# SD_A2.net
KiCad netlist of a schematic drawn in EAGLE
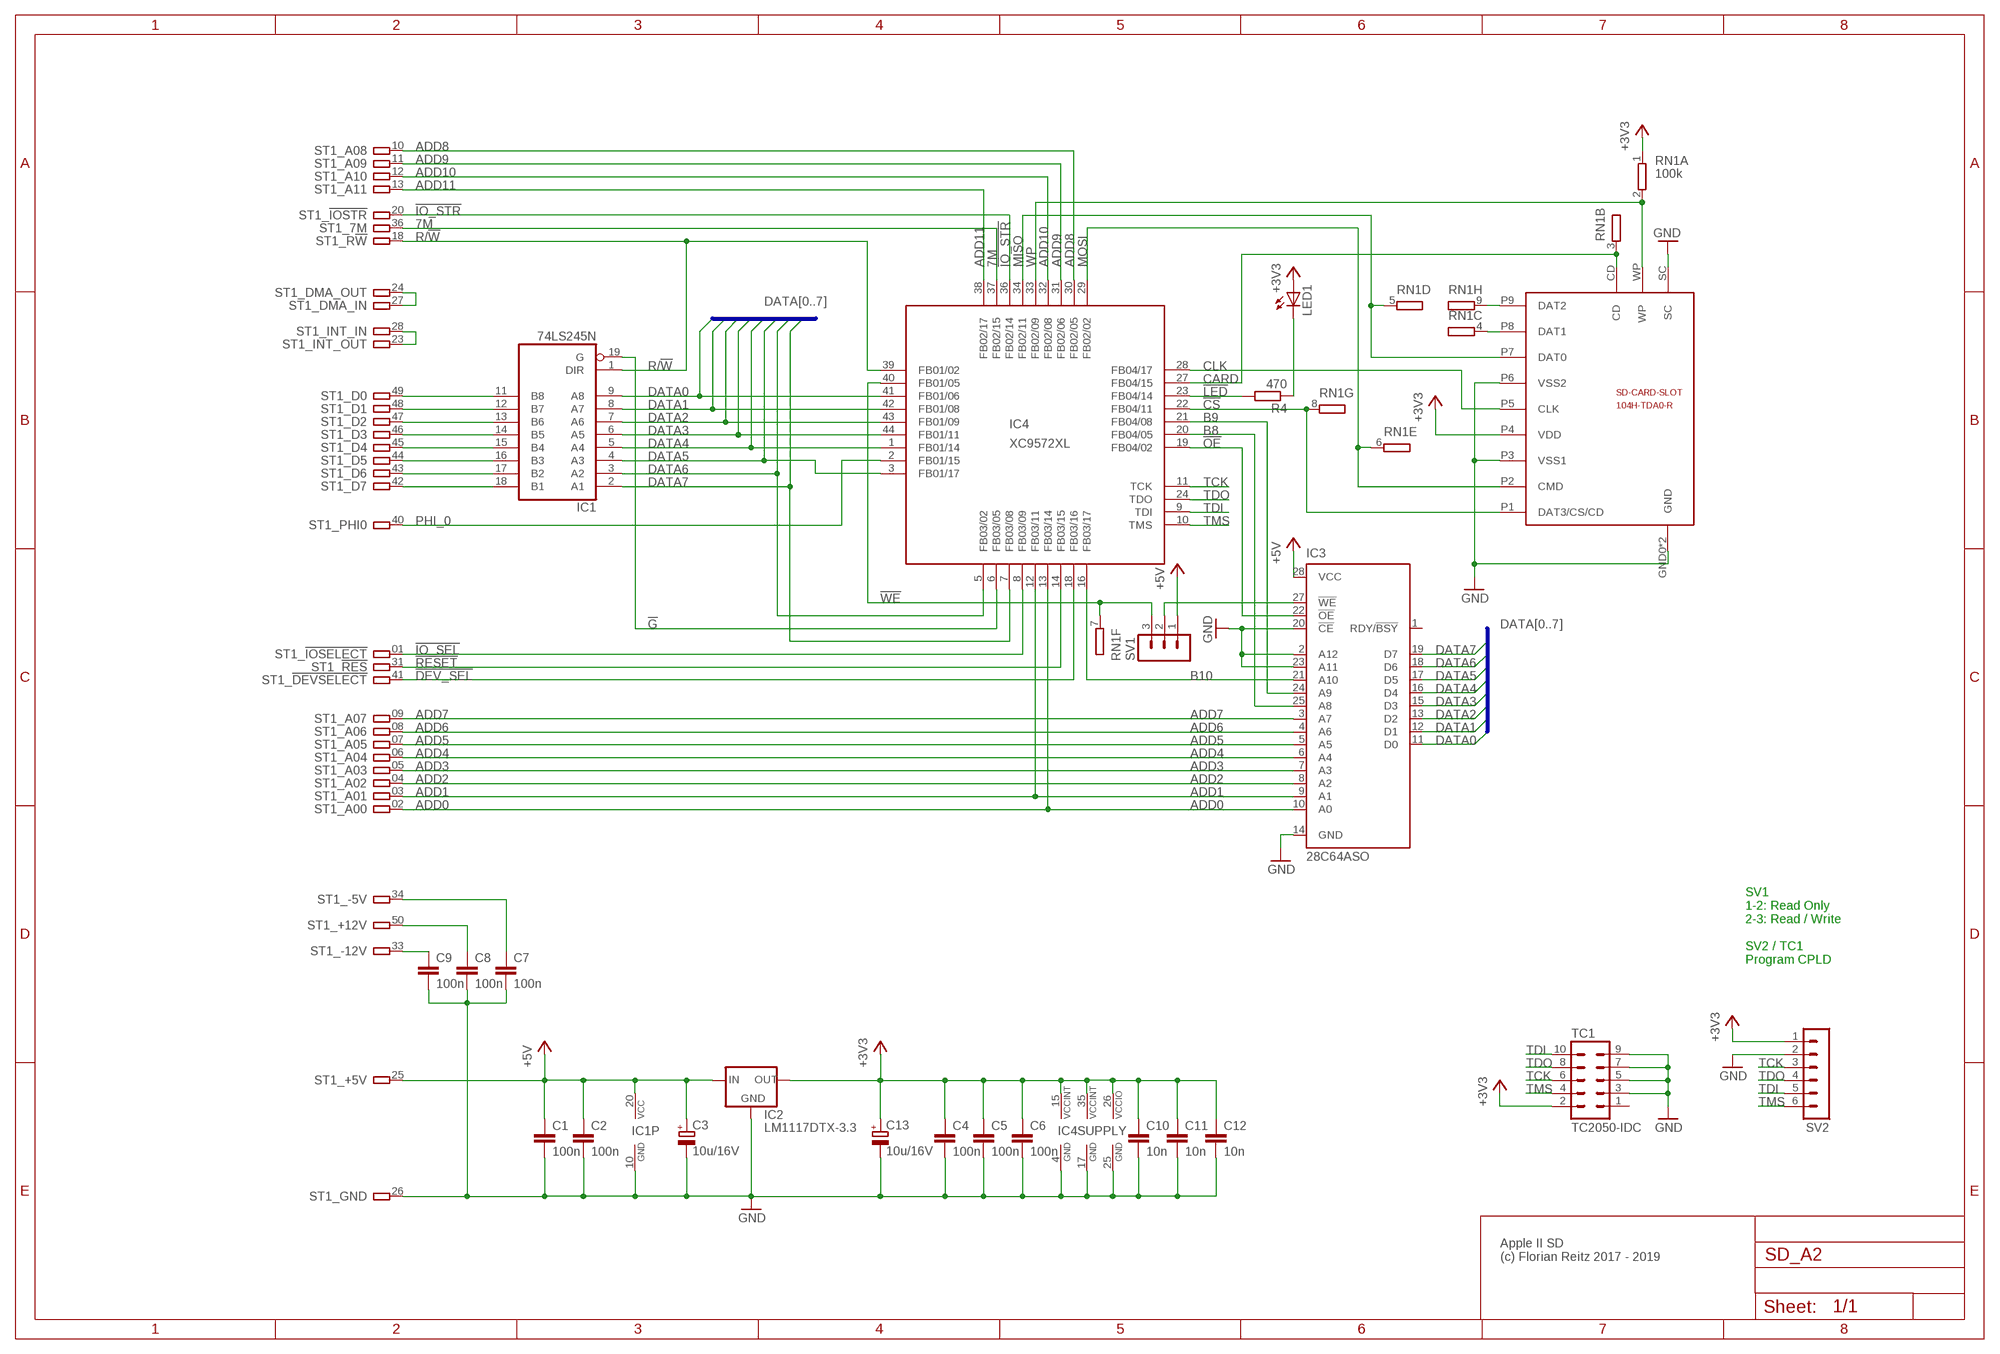
[diagram p0: schematic, sheet 1]

(export (version "E")
  (design (tool "Eeschema 10.0.6"))
  (components
    (comp (ref "C1")
      (value "100n")
      (footprint "eagle-import:C0603K")
      (libsource (lib "eagle-import") (part "C-EUC0603K"))
    )
    (comp (ref "C2")
      (value "100n")
      (footprint "eagle-import:C0603K")
      (libsource (lib "eagle-import") (part "C-EUC0603K"))
    )
    (comp (ref "C3")
      (value "10u/16V")
      (footprint "eagle-import:A_3216-18R")
      (libsource (lib "eagle-import") (part "CPOL-EUA/3216-18R"))
    )
    (comp (ref "C4")
      (value "100n")
      (footprint "eagle-import:C0603K")
      (libsource (lib "eagle-import") (part "C-EUC0603K"))
    )
    (comp (ref "C5")
      (value "100n")
      (footprint "eagle-import:C0603K")
      (libsource (lib "eagle-import") (part "C-EUC0603K"))
    )
    (comp (ref "C6")
      (value "100n")
      (footprint "eagle-import:C0603K")
      (libsource (lib "eagle-import") (part "C-EUC0603K"))
    )
    (comp (ref "C7")
      (value "100n")
      (footprint "eagle-import:C0603K")
      (libsource (lib "eagle-import") (part "C-EUC0603K"))
    )
    (comp (ref "C8")
      (value "100n")
      (footprint "eagle-import:C0603K")
      (libsource (lib "eagle-import") (part "C-EUC0603K"))
    )
    (comp (ref "C9")
      (value "100n")
      (footprint "eagle-import:C0603K")
      (libsource (lib "eagle-import") (part "C-EUC0603K"))
    )
    (comp (ref "C10")
      (value "10n")
      (footprint "eagle-import:C0603K")
      (libsource (lib "eagle-import") (part "C-EUC0603K"))
    )
    (comp (ref "C11")
      (value "10n")
      (footprint "eagle-import:C0603K")
      (libsource (lib "eagle-import") (part "C-EUC0603K"))
    )
    (comp (ref "C12")
      (value "10n")
      (footprint "eagle-import:C0603K")
      (libsource (lib "eagle-import") (part "C-EUC0603K"))
    )
    (comp (ref "C13")
      (value "10u/16V")
      (footprint "eagle-import:A_3216-18R")
      (libsource (lib "eagle-import") (part "CPOL-EUA/3216-18R"))
    )
    (comp (ref "IC1")
      (value "74LS245N")
      (footprint "eagle-import:DIL20")
      (libsource (lib "eagle-import") (part "74245NLS"))
    )
    (comp (ref "IC2")
      (value "LM1117DTX-3.3")
      (footprint "eagle-import:TO252")
      (libsource (lib "eagle-import") (part "LM1117DTX-3.3"))
    )
    (comp (ref "IC3")
      (value "28C64ASO")
      (footprint "eagle-import:SO28W")
      (fields (field (name "MPN") "CAT28C64BWI-12"))
      (libsource (lib "eagle-import") (part "2864ASOC"))
    )
    (comp (ref "IC4")
      (value "XC9572XL")
      (footprint "eagle-import:SQFP-S-10X10-44")
      (libsource (lib "eagle-import") (part "XC9572_S44VQFP"))
    )
    (comp (ref "LED1")
      (value "LEDSQR2X5")
      (footprint "eagle-import:LED2X5")
      (libsource (lib "eagle-import") (part "LEDSQR2X5"))
    )
    (comp (ref "R4")
      (value "470")
      (footprint "eagle-import:R0603")
      (libsource (lib "eagle-import") (part "R-EU_R0603"))
    )
    (comp (ref "RN1")
      (value "100k")
      (footprint "eagle-import:SIL9")
      (libsource (lib "eagle-import") (part "GE08R"))
    )
    (comp (ref "ST1")
      (value "A2-50PINSLOT1-3")
      (footprint "eagle-import:A2-50PIN-SL1-3")
      (libsource (lib "eagle-import") (part "A2-50PINSLOT1-3"))
    )
    (comp (ref "SV1")
      (value "MA03-1")
      (footprint "eagle-import:MA03-1")
      (libsource (lib "eagle-import") (part "MA03-1"))
    )
    (comp (ref "SV2")
      (value "MA06-1")
      (footprint "eagle-import:MA06-1")
      (libsource (lib "eagle-import") (part "MA06-1"))
    )
    (comp (ref "TC1")
      (value "TC2050-IDC")
      (footprint "eagle-import:TC2050-IDC")
      (libsource (lib "eagle-import") (part "TC2050-IDC"))
    )
    (comp (ref "U$2")
      (value "104H-TDA0-R")
      (footprint "eagle-import:104H-TDA0-R")
      (libsource (lib "eagle-import") (part "104H-TDA0-R"))
    )
  )
  (nets
    (net (code "1") (name "+3V3") (class "Default")
      (node (ref "C10") (pin "1") (pinfunction "1_1") (pintype "passive"))
      (node (ref "C11") (pin "1") (pinfunction "1_1") (pintype "passive"))
      (node (ref "C12") (pin "1") (pinfunction "1_1") (pintype "passive"))
      (node (ref "C13") (pin "+") (pinfunction "+_+") (pintype "passive"))
      (node (ref "C4") (pin "1") (pinfunction "1_1") (pintype "passive"))
      (node (ref "C5") (pin "1") (pinfunction "1_1") (pintype "passive"))
      (node (ref "C6") (pin "1") (pinfunction "1_1") (pintype "passive"))
      (node (ref "IC2") (pin "TAB") (pinfunction "OUT_TAB") (pintype "passive"))
      (node (ref "IC4") (pin "15") (pinfunction "VCCINT_15") (pintype "power_in"))
      (node (ref "IC4") (pin "26") (pinfunction "VCCIO_26") (pintype "power_in"))
      (node (ref "IC4") (pin "35") (pinfunction "VCCINT_35") (pintype "power_in"))
      (node (ref "LED1") (pin "A") (pinfunction "A_A") (pintype "passive"))
      (node (ref "RN1") (pin "1") (pinfunction "1_1") (pintype "passive"))
      (node (ref "SV2") (pin "1") (pinfunction "1_1") (pintype "passive"))
      (node (ref "TC1") (pin "2") (pinfunction "2_2") (pintype "passive"))
      (node (ref "U$2") (pin "P4") (pinfunction "VDD_P4") (pintype "bidirectional"))
    )
    (net (code "2") (name "+5V") (class "Default")
      (node (ref "C1") (pin "1") (pinfunction "1_1") (pintype "passive"))
      (node (ref "C2") (pin "1") (pinfunction "1_1") (pintype "passive"))
      (node (ref "C3") (pin "+") (pinfunction "+_+") (pintype "passive"))
      (node (ref "IC1") (pin "20") (pinfunction "VCC_20") (pintype "power_in"))
      (node (ref "IC2") (pin "2") (pinfunction "IN_2") (pintype "input"))
      (node (ref "IC3") (pin "28") (pinfunction "VCC_28") (pintype "power_in"))
      (node (ref "ST1") (pin "25") (pinfunction "P_25") (pintype "bidirectional"))
      (node (ref "SV1") (pin "1") (pinfunction "1_1") (pintype "passive"))
    )
    (net (code "3") (name "/7M") (class "Default")
      (node (ref "IC4") (pin "37") (pinfunction "FB02/15_37") (pintype "bidirectional"))
      (node (ref "ST1") (pin "36") (pinfunction "P_36") (pintype "bidirectional"))
    )
    (net (code "4") (name "/ADD0") (class "Default")
      (node (ref "IC3") (pin "10") (pinfunction "A0_10") (pintype "input"))
      (node (ref "IC4") (pin "13") (pinfunction "FB03/14_13") (pintype "bidirectional"))
      (node (ref "ST1") (pin "02") (pinfunction "P_02") (pintype "bidirectional"))
    )
    (net (code "5") (name "/ADD1") (class "Default")
      (node (ref "IC3") (pin "9") (pinfunction "A1_9") (pintype "input"))
      (node (ref "IC4") (pin "12") (pinfunction "FB03/11_12") (pintype "bidirectional"))
      (node (ref "ST1") (pin "03") (pinfunction "P_03") (pintype "bidirectional"))
    )
    (net (code "6") (name "/ADD2") (class "Default")
      (node (ref "IC3") (pin "8") (pinfunction "A2_8") (pintype "input"))
      (node (ref "ST1") (pin "04") (pinfunction "P_04") (pintype "bidirectional"))
    )
    (net (code "7") (name "/ADD3") (class "Default")
      (node (ref "IC3") (pin "7") (pinfunction "A3_7") (pintype "input"))
      (node (ref "ST1") (pin "05") (pinfunction "P_05") (pintype "bidirectional"))
    )
    (net (code "8") (name "/ADD4") (class "Default")
      (node (ref "IC3") (pin "6") (pinfunction "A4_6") (pintype "input"))
      (node (ref "ST1") (pin "06") (pinfunction "P_06") (pintype "bidirectional"))
    )
    (net (code "9") (name "/ADD5") (class "Default")
      (node (ref "IC3") (pin "5") (pinfunction "A5_5") (pintype "input"))
      (node (ref "ST1") (pin "07") (pinfunction "P_07") (pintype "bidirectional"))
    )
    (net (code "10") (name "/ADD6") (class "Default")
      (node (ref "IC3") (pin "4") (pinfunction "A6_4") (pintype "input"))
      (node (ref "ST1") (pin "08") (pinfunction "P_08") (pintype "bidirectional"))
    )
    (net (code "11") (name "/ADD7") (class "Default")
      (node (ref "IC3") (pin "3") (pinfunction "A7_3") (pintype "input"))
      (node (ref "ST1") (pin "09") (pinfunction "P_09") (pintype "bidirectional"))
    )
    (net (code "12") (name "/ADD8") (class "Default")
      (node (ref "IC4") (pin "30") (pinfunction "FB02/05_30") (pintype "bidirectional"))
      (node (ref "ST1") (pin "10") (pinfunction "P_10") (pintype "bidirectional"))
    )
    (net (code "13") (name "/ADD9") (class "Default")
      (node (ref "IC4") (pin "31") (pinfunction "FB02/06_31") (pintype "bidirectional"))
      (node (ref "ST1") (pin "11") (pinfunction "P_11") (pintype "bidirectional"))
    )
    (net (code "14") (name "/ADD10") (class "Default")
      (node (ref "IC4") (pin "32") (pinfunction "FB02/08_32") (pintype "bidirectional"))
      (node (ref "ST1") (pin "12") (pinfunction "P_12") (pintype "bidirectional"))
    )
    (net (code "15") (name "/ADD11") (class "Default")
      (node (ref "IC4") (pin "38") (pinfunction "FB02/17_38") (pintype "bidirectional"))
      (node (ref "ST1") (pin "13") (pinfunction "P_13") (pintype "bidirectional"))
    )
    (net (code "16") (name "/B8") (class "Default")
      (node (ref "IC3") (pin "25") (pinfunction "A8_25") (pintype "input"))
      (node (ref "IC4") (pin "20") (pinfunction "FB04/05_20") (pintype "bidirectional"))
    )
    (net (code "17") (name "/B9") (class "Default")
      (node (ref "IC3") (pin "24") (pinfunction "A9_24") (pintype "input"))
      (node (ref "IC4") (pin "21") (pinfunction "FB04/08_21") (pintype "bidirectional"))
    )
    (net (code "18") (name "/B10") (class "Default")
      (node (ref "IC3") (pin "21") (pinfunction "A10_21") (pintype "input"))
      (node (ref "IC4") (pin "16") (pinfunction "FB03/17_16") (pintype "bidirectional"))
    )
    (net (code "19") (name "/CARD") (class "Default")
      (node (ref "IC4") (pin "27") (pinfunction "FB04/15_27") (pintype "bidirectional"))
      (node (ref "RN1") (pin "3") (pinfunction "2_3") (pintype "passive"))
      (node (ref "U$2") (pin "CD") (pinfunction "CD_CD") (pintype "bidirectional"))
    )
    (net (code "20") (name "/CLK") (class "Default")
      (node (ref "IC4") (pin "28") (pinfunction "FB04/17_28") (pintype "bidirectional"))
      (node (ref "U$2") (pin "P5") (pinfunction "CLK_P5") (pintype "bidirectional"))
    )
    (net (code "21") (name "/DATA0") (class "Default")
      (node (ref "IC1") (pin "9") (pinfunction "A8_9") (pintype "bidirectional"))
      (node (ref "IC3") (pin "11") (pinfunction "D0_11") (pintype "tri_state"))
      (node (ref "IC4") (pin "41") (pinfunction "FB01/06_41") (pintype "bidirectional"))
    )
    (net (code "22") (name "/DATA1") (class "Default")
      (node (ref "IC1") (pin "8") (pinfunction "A7_8") (pintype "bidirectional"))
      (node (ref "IC3") (pin "12") (pinfunction "D1_12") (pintype "tri_state"))
      (node (ref "IC4") (pin "42") (pinfunction "FB01/08_42") (pintype "bidirectional"))
    )
    (net (code "23") (name "/DATA2") (class "Default")
      (node (ref "IC1") (pin "7") (pinfunction "A6_7") (pintype "bidirectional"))
      (node (ref "IC3") (pin "13") (pinfunction "D2_13") (pintype "tri_state"))
      (node (ref "IC4") (pin "43") (pinfunction "FB01/09_43") (pintype "bidirectional"))
    )
    (net (code "24") (name "/DATA3") (class "Default")
      (node (ref "IC1") (pin "6") (pinfunction "A5_6") (pintype "bidirectional"))
      (node (ref "IC3") (pin "15") (pinfunction "D3_15") (pintype "tri_state"))
      (node (ref "IC4") (pin "44") (pinfunction "FB01/11_44") (pintype "bidirectional"))
    )
    (net (code "25") (name "/DATA4") (class "Default")
      (node (ref "IC1") (pin "5") (pinfunction "A4_5") (pintype "bidirectional"))
      (node (ref "IC3") (pin "16") (pinfunction "D4_16") (pintype "tri_state"))
      (node (ref "IC4") (pin "1") (pinfunction "FB01/14_1") (pintype "bidirectional"))
    )
    (net (code "26") (name "/DATA5") (class "Default")
      (node (ref "IC1") (pin "4") (pinfunction "A3_4") (pintype "bidirectional"))
      (node (ref "IC3") (pin "17") (pinfunction "D5_17") (pintype "tri_state"))
      (node (ref "IC4") (pin "3") (pinfunction "FB01/17_3") (pintype "bidirectional"))
    )
    (net (code "27") (name "/DATA6") (class "Default")
      (node (ref "IC1") (pin "3") (pinfunction "A2_3") (pintype "bidirectional"))
      (node (ref "IC3") (pin "18") (pinfunction "D6_18") (pintype "tri_state"))
      (node (ref "IC4") (pin "5") (pinfunction "FB03/02_5") (pintype "bidirectional"))
    )
    (net (code "28") (name "/DATA7") (class "Default")
      (node (ref "IC1") (pin "2") (pinfunction "A1_2") (pintype "bidirectional"))
      (node (ref "IC3") (pin "19") (pinfunction "D7_19") (pintype "tri_state"))
      (node (ref "IC4") (pin "7") (pinfunction "FB03/08_7") (pintype "bidirectional"))
    )
    (net (code "30") (name "/MISO") (class "Default")
      (node (ref "IC4") (pin "34") (pinfunction "FB02/11_34") (pintype "bidirectional"))
      (node (ref "RN1") (pin "5") (pinfunction "2_5") (pintype "passive"))
      (node (ref "U$2") (pin "P7") (pinfunction "DAT0_P7") (pintype "bidirectional"))
    )
    (net (code "31") (name "/MOSI") (class "Default")
      (node (ref "IC4") (pin "29") (pinfunction "FB02/02_29") (pintype "bidirectional"))
      (node (ref "RN1") (pin "6") (pinfunction "2_6") (pintype "passive"))
      (node (ref "U$2") (pin "P2") (pinfunction "CMD_P2") (pintype "bidirectional"))
    )
    (net (code "32") (name "/PHI_0") (class "Default")
      (node (ref "IC4") (pin "2") (pinfunction "FB01/15_2") (pintype "bidirectional"))
      (node (ref "ST1") (pin "40") (pinfunction "P_40") (pintype "bidirectional"))
    )
    (net (code "33") (name "/R{slash}~{W}") (class "Default")
      (node (ref "IC1") (pin "1") (pinfunction "DIR_1") (pintype "input"))
      (node (ref "IC4") (pin "39") (pinfunction "FB01/02_39") (pintype "bidirectional"))
      (node (ref "ST1") (pin "18") (pinfunction "P_18") (pintype "bidirectional"))
    )
    (net (code "34") (name "/TCK") (class "Default")
      (node (ref "IC4") (pin "11") (pinfunction "TCK_11") (pintype "input"))
      (node (ref "SV2") (pin "3") (pinfunction "3_3") (pintype "passive"))
      (node (ref "TC1") (pin "6") (pinfunction "6_6") (pintype "passive"))
    )
    (net (code "35") (name "/TDI") (class "Default")
      (node (ref "IC4") (pin "9") (pinfunction "TDI_9") (pintype "input"))
      (node (ref "SV2") (pin "5") (pinfunction "5_5") (pintype "passive"))
      (node (ref "TC1") (pin "10") (pinfunction "10_10") (pintype "passive"))
    )
    (net (code "36") (name "/TDO") (class "Default")
      (node (ref "IC4") (pin "24") (pinfunction "TDO_24") (pintype "output"))
      (node (ref "SV2") (pin "4") (pinfunction "4_4") (pintype "passive"))
      (node (ref "TC1") (pin "8") (pinfunction "8_8") (pintype "passive"))
    )
    (net (code "37") (name "/TMS") (class "Default")
      (node (ref "IC4") (pin "10") (pinfunction "TMS_10") (pintype "input"))
      (node (ref "SV2") (pin "6") (pinfunction "6_6") (pintype "passive"))
      (node (ref "TC1") (pin "4") (pinfunction "4_4") (pintype "passive"))
    )
    (net (code "38") (name "/WP") (class "Default")
      (node (ref "IC4") (pin "33") (pinfunction "FB02/09_33") (pintype "bidirectional"))
      (node (ref "RN1") (pin "2") (pinfunction "2_2") (pintype "passive"))
      (node (ref "U$2") (pin "WP") (pinfunction "WP_WP") (pintype "bidirectional"))
    )
    (net (code "39") (name "/~{CS}") (class "Default")
      (node (ref "IC4") (pin "22") (pinfunction "FB04/11_22") (pintype "bidirectional"))
      (node (ref "RN1") (pin "8") (pinfunction "2_8") (pintype "passive"))
      (node (ref "U$2") (pin "P1") (pinfunction "DAT3/CS/CD_P1") (pintype "bidirectional"))
    )
    (net (code "40") (name "/~{DEV_SEL}") (class "Default")
      (node (ref "IC4") (pin "18") (pinfunction "FB03/16_18") (pintype "bidirectional"))
      (node (ref "ST1") (pin "41") (pinfunction "P_41") (pintype "bidirectional"))
    )
    (net (code "41") (name "/~{G}") (class "Default")
      (node (ref "IC1") (pin "19") (pinfunction "G_19") (pintype "input"))
      (node (ref "IC4") (pin "6") (pinfunction "FB03/05_6") (pintype "bidirectional"))
    )
    (net (code "42") (name "/~{IO_SEL}") (class "Default")
      (node (ref "IC4") (pin "8") (pinfunction "FB03/09_8") (pintype "bidirectional"))
      (node (ref "ST1") (pin "01") (pinfunction "P_01") (pintype "bidirectional"))
    )
    (net (code "43") (name "/~{IO_STR}") (class "Default")
      (node (ref "IC4") (pin "36") (pinfunction "FB02/14_36") (pintype "bidirectional"))
      (node (ref "ST1") (pin "20") (pinfunction "P_20") (pintype "bidirectional"))
    )
    (net (code "44") (name "/~{LED}") (class "Default")
      (node (ref "IC4") (pin "23") (pinfunction "FB04/14_23") (pintype "bidirectional"))
      (node (ref "R4") (pin "2") (pinfunction "2_2") (pintype "passive"))
    )
    (net (code "45") (name "/~{OE}") (class "Default")
      (node (ref "IC3") (pin "22") (pinfunction "~{OE}_22") (pintype "input"))
      (node (ref "IC4") (pin "19") (pinfunction "FB04/02_19") (pintype "bidirectional"))
    )
    (net (code "46") (name "/~{RESET}") (class "Default")
      (node (ref "IC4") (pin "14") (pinfunction "FB03/15_14") (pintype "bidirectional"))
      (node (ref "ST1") (pin "31") (pinfunction "P_31") (pintype "bidirectional"))
    )
    (net (code "47") (name "/~{WE}") (class "Default")
      (node (ref "IC4") (pin "40") (pinfunction "FB01/05_40") (pintype "bidirectional"))
      (node (ref "RN1") (pin "7") (pinfunction "2_7") (pintype "passive"))
      (node (ref "SV1") (pin "3") (pinfunction "3_3") (pintype "passive"))
    )
    (net (code "48") (name "GND") (class "Default")
      (node (ref "C1") (pin "2") (pinfunction "2_2") (pintype "passive"))
      (node (ref "C10") (pin "2") (pinfunction "2_2") (pintype "passive"))
      (node (ref "C11") (pin "2") (pinfunction "2_2") (pintype "passive"))
      (node (ref "C12") (pin "2") (pinfunction "2_2") (pintype "passive"))
      (node (ref "C13") (pin "-") (pinfunction "-_-") (pintype "passive"))
      (node (ref "C2") (pin "2") (pinfunction "2_2") (pintype "passive"))
      (node (ref "C3") (pin "-") (pinfunction "-_-") (pintype "passive"))
      (node (ref "C4") (pin "2") (pinfunction "2_2") (pintype "passive"))
      (node (ref "C5") (pin "2") (pinfunction "2_2") (pintype "passive"))
      (node (ref "C6") (pin "2") (pinfunction "2_2") (pintype "passive"))
      (node (ref "C7") (pin "2") (pinfunction "2_2") (pintype "passive"))
      (node (ref "C8") (pin "2") (pinfunction "2_2") (pintype "passive"))
      (node (ref "C9") (pin "2") (pinfunction "2_2") (pintype "passive"))
      (node (ref "IC1") (pin "10") (pinfunction "GND_10") (pintype "power_in"))
      (node (ref "IC2") (pin "1") (pinfunction "GND_1") (pintype "input"))
      (node (ref "IC3") (pin "14") (pinfunction "GND_14") (pintype "power_in"))
      (node (ref "IC3") (pin "2") (pinfunction "A12_2") (pintype "input"))
      (node (ref "IC3") (pin "20") (pinfunction "~{CE}_20") (pintype "input"))
      (node (ref "IC3") (pin "23") (pinfunction "A11_23") (pintype "input"))
      (node (ref "IC4") (pin "17") (pinfunction "GND_17") (pintype "power_in"))
      (node (ref "IC4") (pin "25") (pinfunction "GND_25") (pintype "power_in"))
      (node (ref "IC4") (pin "4") (pinfunction "GND_4") (pintype "power_in"))
      (node (ref "ST1") (pin "26") (pinfunction "P_26") (pintype "bidirectional"))
      (node (ref "SV2") (pin "2") (pinfunction "2_2") (pintype "passive"))
      (node (ref "TC1") (pin "3") (pinfunction "3_3") (pintype "passive"))
      (node (ref "TC1") (pin "5") (pinfunction "5_5") (pintype "passive"))
      (node (ref "TC1") (pin "7") (pinfunction "7_7") (pintype "passive"))
      (node (ref "TC1") (pin "9") (pinfunction "9_9") (pintype "passive"))
      (node (ref "U$2") (pin "GND0") (pinfunction "GND_GND0") (pintype "bidirectional"))
      (node (ref "U$2") (pin "GND1") (pinfunction "GND_GND1") (pintype "bidirectional"))
      (node (ref "U$2") (pin "P3") (pinfunction "VSS1_P3") (pintype "bidirectional"))
      (node (ref "U$2") (pin "P6") (pinfunction "VSS2_P6") (pintype "bidirectional"))
      (node (ref "U$2") (pin "SC") (pinfunction "SC_SC") (pintype "bidirectional"))
    )
    (net (code "49") (name "Net-(IC1A-B1)") (class "Default")
      (node (ref "IC1") (pin "18") (pinfunction "B1_18") (pintype "bidirectional"))
      (node (ref "ST1") (pin "42") (pinfunction "P_42") (pintype "bidirectional"))
    )
    (net (code "50") (name "Net-(IC1A-B2)") (class "Default")
      (node (ref "IC1") (pin "17") (pinfunction "B2_17") (pintype "bidirectional"))
      (node (ref "ST1") (pin "43") (pinfunction "P_43") (pintype "bidirectional"))
    )
    (net (code "51") (name "Net-(IC1A-B3)") (class "Default")
      (node (ref "IC1") (pin "16") (pinfunction "B3_16") (pintype "bidirectional"))
      (node (ref "ST1") (pin "44") (pinfunction "P_44") (pintype "bidirectional"))
    )
    (net (code "52") (name "Net-(IC1A-B4)") (class "Default")
      (node (ref "IC1") (pin "15") (pinfunction "B4_15") (pintype "bidirectional"))
      (node (ref "ST1") (pin "45") (pinfunction "P_45") (pintype "bidirectional"))
    )
    (net (code "53") (name "Net-(IC1A-B5)") (class "Default")
      (node (ref "IC1") (pin "14") (pinfunction "B5_14") (pintype "bidirectional"))
      (node (ref "ST1") (pin "46") (pinfunction "P_46") (pintype "bidirectional"))
    )
    (net (code "54") (name "Net-(IC1A-B6)") (class "Default")
      (node (ref "IC1") (pin "13") (pinfunction "B6_13") (pintype "bidirectional"))
      (node (ref "ST1") (pin "47") (pinfunction "P_47") (pintype "bidirectional"))
    )
    (net (code "55") (name "Net-(IC1A-B7)") (class "Default")
      (node (ref "IC1") (pin "12") (pinfunction "B7_12") (pintype "bidirectional"))
      (node (ref "ST1") (pin "48") (pinfunction "P_48") (pintype "bidirectional"))
    )
    (net (code "56") (name "Net-(IC1A-B8)") (class "Default")
      (node (ref "IC1") (pin "11") (pinfunction "B8_11") (pintype "bidirectional"))
      (node (ref "ST1") (pin "49") (pinfunction "P_49") (pintype "bidirectional"))
    )
    (net (code "57") (name "Net-(IC3-~{WE})") (class "Default")
      (node (ref "IC3") (pin "27") (pinfunction "~{WE}_27") (pintype "input"))
      (node (ref "SV1") (pin "2") (pinfunction "2_2") (pintype "passive"))
    )
    (net (code "58") (name "Net-(LED1-C)") (class "Default")
      (node (ref "LED1") (pin "K") (pinfunction "C_K") (pintype "passive"))
      (node (ref "R4") (pin "1") (pinfunction "1_1") (pintype "passive"))
    )
    (net (code "59") (name "Net-(RN1C-2)") (class "Default")
      (node (ref "RN1") (pin "4") (pinfunction "2_4") (pintype "passive"))
      (node (ref "U$2") (pin "P8") (pinfunction "DAT1_P8") (pintype "bidirectional"))
    )
    (net (code "60") (name "Net-(RN1H-2)") (class "Default")
      (node (ref "RN1") (pin "9") (pinfunction "2_9") (pintype "passive"))
      (node (ref "U$2") (pin "P9") (pinfunction "DAT2_P9") (pintype "bidirectional"))
    )
    (net (code "61") (name "Net-(ST1AL-P)") (class "Default")
      (node (ref "ST1") (pin "24") (pinfunction "P_24") (pintype "bidirectional"))
      (node (ref "ST1") (pin "27") (pinfunction "P_27") (pintype "bidirectional"))
    )
    (net (code "62") (name "Net-(ST1AO-P)") (class "Default")
      (node (ref "ST1") (pin "23") (pinfunction "P_23") (pintype "bidirectional"))
      (node (ref "ST1") (pin "28") (pinfunction "P_28") (pintype "bidirectional"))
    )
    (net (code "63") (name "Net-(ST1I-P)") (class "Default")
      (node (ref "C8") (pin "1") (pinfunction "1_1") (pintype "passive"))
      (node (ref "ST1") (pin "50") (pinfunction "P_50") (pintype "bidirectional"))
    )
    (net (code "64") (name "Net-(ST1K-P)") (class "Default")
      (node (ref "C9") (pin "1") (pinfunction "1_1") (pintype "passive"))
      (node (ref "ST1") (pin "33") (pinfunction "P_33") (pintype "bidirectional"))
    )
    (net (code "65") (name "Net-(ST1L-P)") (class "Default")
      (node (ref "C7") (pin "1") (pinfunction "1_1") (pintype "passive"))
      (node (ref "ST1") (pin "34") (pinfunction "P_34") (pintype "bidirectional"))
    )
    (net (code "66") (name "unconnected-(IC3-RDY{slash}~{BSY}-Pad1)") (class "Default")
      (node (ref "IC3") (pin "1") (pinfunction "RDY/~{BSY}_1") (pintype "output"))
    )
    (net (code "67") (name "unconnected-(TC1-Pad1)") (class "Default")
      (node (ref "TC1") (pin "1") (pinfunction "1_1") (pintype "passive"))
    )
  )
)
